# Skematik.net
KiCad netlist of a schematic drawn in EAGLE
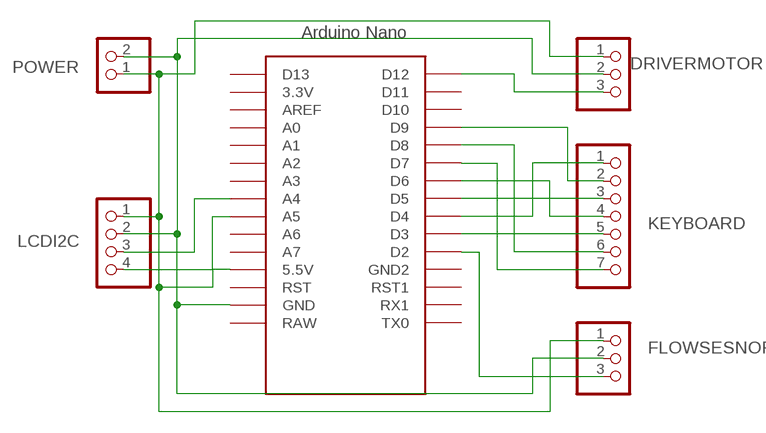
[diagram p0: schematic, sheet 1]

(export (version "E")
  (design (tool "Eeschema 10.0.6"))
  (components
    (comp (ref "DRIVERMOTOR")
      (value "PINHD-1X3")
      (footprint "eagle-import:1X03")
      (libsource (lib "eagle-import") (part "PINHD-1X3"))
    )
    (comp (ref "FLOWSESNOR")
      (value "PINHD-1X3")
      (footprint "eagle-import:1X03")
      (libsource (lib "eagle-import") (part "PINHD-1X3"))
    )
    (comp (ref "KEYBOARD")
      (value "PINHD-1X7")
      (footprint "eagle-import:1X07")
      (libsource (lib "eagle-import") (part "PINHD-1X7"))
    )
    (comp (ref "LCDI2C")
      (value "PINHD-1X4")
      (footprint "eagle-import:1X04")
      (libsource (lib "eagle-import") (part "PINHD-1X4"))
    )
    (comp (ref "POWER")
      (value "PINHD-1X2")
      (footprint "eagle-import:1X02")
      (libsource (lib "eagle-import") (part "PINHD-1X2"))
    )
    (comp (ref "U$1")
      (value "NANO")
      (footprint "eagle-import:NANO")
      (libsource (lib "eagle-import") (part "NANO"))
    )
  )
  (nets
    (net (code "1") (name "Net-(DRIVERMOTOR-Pad2)") (class "Default")
      (node (ref "DRIVERMOTOR") (pin "2") (pinfunction "2_2") (pintype "passive"))
      (node (ref "FLOWSESNOR") (pin "2") (pinfunction "2_2") (pintype "passive"))
      (node (ref "LCDI2C") (pin "2") (pinfunction "2_2") (pintype "passive"))
      (node (ref "POWER") (pin "2") (pinfunction "2_2") (pintype "passive"))
      (node (ref "U$1") (pin "GND") (pinfunction "GND_GND") (pintype "bidirectional"))
    )
    (net (code "2") (name "Net-(DRIVERMOTOR-Pad3)") (class "Default")
      (node (ref "DRIVERMOTOR") (pin "3") (pinfunction "3_3") (pintype "passive"))
      (node (ref "U$1") (pin "D12") (pinfunction "D12_D12") (pintype "bidirectional"))
    )
    (net (code "3") (name "Net-(FLOWSESNOR-Pad3)") (class "Default")
      (node (ref "FLOWSESNOR") (pin "3") (pinfunction "3_3") (pintype "passive"))
      (node (ref "U$1") (pin "D2") (pinfunction "D2_D2") (pintype "bidirectional"))
    )
    (net (code "4") (name "Net-(KEYBOARD-Pad1)") (class "Default")
      (node (ref "KEYBOARD") (pin "1") (pinfunction "1_1") (pintype "passive"))
      (node (ref "U$1") (pin "D4") (pinfunction "D4_D4") (pintype "bidirectional"))
    )
    (net (code "5") (name "Net-(KEYBOARD-Pad2)") (class "Default")
      (node (ref "KEYBOARD") (pin "2") (pinfunction "2_2") (pintype "passive"))
      (node (ref "U$1") (pin "D9") (pinfunction "D9_D9") (pintype "bidirectional"))
    )
    (net (code "6") (name "Net-(KEYBOARD-Pad3)") (class "Default")
      (node (ref "KEYBOARD") (pin "3") (pinfunction "3_3") (pintype "passive"))
      (node (ref "U$1") (pin "D5") (pinfunction "D5_D5") (pintype "bidirectional"))
    )
    (net (code "7") (name "Net-(KEYBOARD-Pad4)") (class "Default")
      (node (ref "KEYBOARD") (pin "4") (pinfunction "4_4") (pintype "passive"))
      (node (ref "U$1") (pin "D6") (pinfunction "D6_D6") (pintype "bidirectional"))
    )
    (net (code "8") (name "Net-(KEYBOARD-Pad5)") (class "Default")
      (node (ref "KEYBOARD") (pin "5") (pinfunction "5_5") (pintype "passive"))
      (node (ref "U$1") (pin "D3") (pinfunction "D3_D3") (pintype "bidirectional"))
    )
    (net (code "9") (name "Net-(KEYBOARD-Pad6)") (class "Default")
      (node (ref "KEYBOARD") (pin "6") (pinfunction "6_6") (pintype "passive"))
      (node (ref "U$1") (pin "D8") (pinfunction "D8_D8") (pintype "bidirectional"))
    )
    (net (code "10") (name "Net-(KEYBOARD-Pad7)") (class "Default")
      (node (ref "KEYBOARD") (pin "7") (pinfunction "7_7") (pintype "passive"))
      (node (ref "U$1") (pin "D7") (pinfunction "D7_D7") (pintype "bidirectional"))
    )
    (net (code "11") (name "Net-(LCDI2C-Pad3)") (class "Default")
      (node (ref "LCDI2C") (pin "3") (pinfunction "3_3") (pintype "passive"))
      (node (ref "U$1") (pin "A4") (pinfunction "A4_A4") (pintype "bidirectional"))
    )
    (net (code "12") (name "Net-(U$1-5.5V)") (class "Default")
      (node (ref "DRIVERMOTOR") (pin "1") (pinfunction "1_1") (pintype "passive"))
      (node (ref "FLOWSESNOR") (pin "1") (pinfunction "1_1") (pintype "passive"))
      (node (ref "LCDI2C") (pin "1") (pinfunction "1_1") (pintype "passive"))
      (node (ref "LCDI2C") (pin "4") (pinfunction "4_4") (pintype "passive"))
      (node (ref "POWER") (pin "1") (pinfunction "1_1") (pintype "passive"))
      (node (ref "U$1") (pin "5V") (pinfunction "5.5V_5V") (pintype "bidirectional"))
      (node (ref "U$1") (pin "A5") (pinfunction "A5_A5") (pintype "bidirectional"))
    )
    (net (code "13") (name "unconnected-(U$1-GND2-PadGND1)") (class "Default")
      (node (ref "U$1") (pin "GND1") (pinfunction "GND2_GND1") (pintype "bidirectional"))
    )
    (net (code "14") (name "unconnected-(U$1-Pad3.3V)") (class "Default")
      (node (ref "U$1") (pin "3.3V") (pinfunction "3.3V_3.3V") (pintype "bidirectional"))
    )
    (net (code "15") (name "unconnected-(U$1-PadA0)") (class "Default")
      (node (ref "U$1") (pin "A0") (pinfunction "A0_A0") (pintype "bidirectional"))
    )
    (net (code "16") (name "unconnected-(U$1-PadA1)") (class "Default")
      (node (ref "U$1") (pin "A1") (pinfunction "A1_A1") (pintype "bidirectional"))
    )
    (net (code "17") (name "unconnected-(U$1-PadA2)") (class "Default")
      (node (ref "U$1") (pin "A2") (pinfunction "A2_A2") (pintype "bidirectional"))
    )
    (net (code "18") (name "unconnected-(U$1-PadA3)") (class "Default")
      (node (ref "U$1") (pin "A3") (pinfunction "A3_A3") (pintype "bidirectional"))
    )
    (net (code "19") (name "unconnected-(U$1-PadA6)") (class "Default")
      (node (ref "U$1") (pin "A6") (pinfunction "A6_A6") (pintype "bidirectional"))
    )
    (net (code "20") (name "unconnected-(U$1-PadA7)") (class "Default")
      (node (ref "U$1") (pin "A7") (pinfunction "A7_A7") (pintype "bidirectional"))
    )
    (net (code "21") (name "unconnected-(U$1-PadAREF)") (class "Default")
      (node (ref "U$1") (pin "AREF") (pinfunction "AREF_AREF") (pintype "bidirectional"))
    )
    (net (code "22") (name "unconnected-(U$1-PadD10)") (class "Default")
      (node (ref "U$1") (pin "D10") (pinfunction "D10_D10") (pintype "bidirectional"))
    )
    (net (code "23") (name "unconnected-(U$1-PadD11)") (class "Default")
      (node (ref "U$1") (pin "D11") (pinfunction "D11_D11") (pintype "bidirectional"))
    )
    (net (code "24") (name "unconnected-(U$1-PadD13)") (class "Default")
      (node (ref "U$1") (pin "D13") (pinfunction "D13_D13") (pintype "bidirectional"))
    )
    (net (code "25") (name "unconnected-(U$1-PadICSP1)") (class "Default")
      (node (ref "U$1") (pin "ICSP1") (pinfunction "ICSP1_ICSP1") (pintype "bidirectional"))
    )
    (net (code "26") (name "unconnected-(U$1-PadICSP2)") (class "Default")
      (node (ref "U$1") (pin "ICSP2") (pinfunction "ICSP2_ICSP2") (pintype "bidirectional"))
    )
    (net (code "27") (name "unconnected-(U$1-PadICSP3)") (class "Default")
      (node (ref "U$1") (pin "ICSP3") (pinfunction "ICSP3_ICSP3") (pintype "bidirectional"))
    )
    (net (code "28") (name "unconnected-(U$1-PadICSP4)") (class "Default")
      (node (ref "U$1") (pin "ICSP4") (pinfunction "ICSP4_ICSP4") (pintype "bidirectional"))
    )
    (net (code "29") (name "unconnected-(U$1-PadICSP5)") (class "Default")
      (node (ref "U$1") (pin "ICSP5") (pinfunction "ICSP5_ICSP5") (pintype "bidirectional"))
    )
    (net (code "30") (name "unconnected-(U$1-PadICSP6)") (class "Default")
      (node (ref "U$1") (pin "ICSP6") (pinfunction "ICSP6_ICSP6") (pintype "bidirectional"))
    )
    (net (code "31") (name "unconnected-(U$1-PadRAW)") (class "Default")
      (node (ref "U$1") (pin "RAW") (pinfunction "RAW_RAW") (pintype "bidirectional"))
    )
    (net (code "32") (name "unconnected-(U$1-PadRST)") (class "Default")
      (node (ref "U$1") (pin "RST") (pinfunction "RST_RST") (pintype "bidirectional"))
    )
    (net (code "33") (name "unconnected-(U$1-PadRST1)") (class "Default")
      (node (ref "U$1") (pin "RST1") (pinfunction "RST1_RST1") (pintype "bidirectional"))
    )
    (net (code "34") (name "unconnected-(U$1-PadRX1)") (class "Default")
      (node (ref "U$1") (pin "RX1") (pinfunction "RX1_RX1") (pintype "bidirectional"))
    )
    (net (code "35") (name "unconnected-(U$1-PadTX0)") (class "Default")
      (node (ref "U$1") (pin "TX0") (pinfunction "TX0_TX0") (pintype "bidirectional"))
    )
  )
)
